# Breadboard_main.net
KiCad netlist of a schematic drawn in Altium Designer
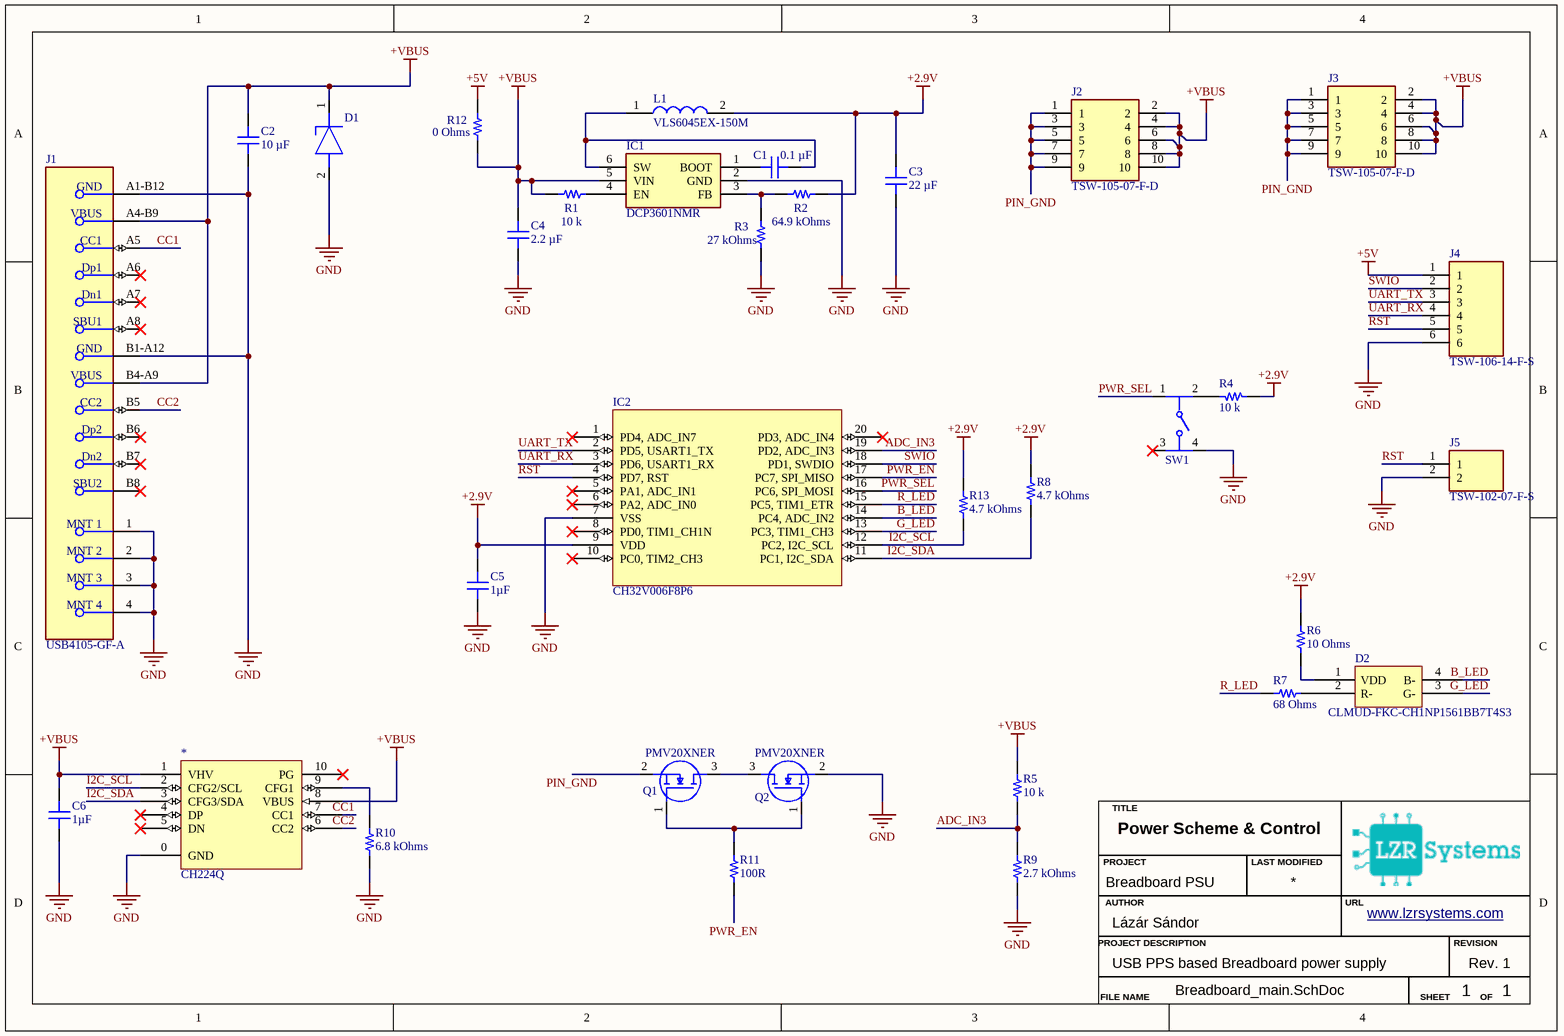
[diagram p0: Breadboard_main.SchDoc]

(export (version "E")
  (design (tool "Eeschema 10.0.6"))
  (components
    (comp (ref "*")
      (value "CH224Q")
      (footprint "SON40P200X75_HS-11N")
      (description "USB-PD 3.2 Sink Controller, EPR, PPS, AVS, I2C")
      (libsource (lib "Sandor Lazar") (part "New symbol 1"))
    )
    (comp (ref "C1")
      (value "0.1 µF")
      (footprint "CAP 0805_2012")
      (description "CAP CER 0.1UF 50V X7R 0805")
      (fields
        (field (name "PART NUMBER") "CC0805MRX7R9BB104")
        (field (name "CAPACITANCE") "0.1 µF")
        (field (name "MANUFACTURER") "Yageo")
      )
      (libsource (lib "Celestial Altium Library - altium_library") (part "Capacitor"))
    )
    (comp (ref "C2")
      (value "10 µF")
      (footprint "CAP 1206_3216 - 0.8MM")
      (description "CAP CER 10UF 25V X5R 1206")
      (fields
        (field (name "PART NUMBER") "TMK316ABJ106KD-T")
        (field (name "CAPACITANCE") "10 µF")
        (field (name "MANUFACTURER") "Taiyo Yuden")
      )
      (libsource (lib "Celestial Altium Library - altium_library") (part "Capacitor"))
    )
    (comp (ref "C3")
      (value "22 µF")
      (footprint "CAP 1206_3216 - 0.8MM")
      (description "CAP CER 22UF 16V X5R 1206")
      (fields
        (field (name "PART NUMBER") "CL31A226MOCLNNC")
        (field (name "CAPACITANCE") "22 µF")
        (field (name "MANUFACTURER") "Samsung Electro-Mechanics")
      )
      (libsource (lib "Celestial Altium Library - altium_library") (part "Capacitor"))
    )
    (comp (ref "C4")
      (value "2.2 µF")
      (footprint "CAP 1206_3216 - 0.8MM")
      (description "CAP CER 2.2UF 50V X7R 1206")
      (fields
        (field (name "PART NUMBER") "GCJ31CR71H225KA12K")
        (field (name "CAPACITANCE") "2.2 µF")
        (field (name "MANUFACTURER") "Murata Electronics")
      )
      (libsource (lib "Celestial Altium Library - altium_library") (part "Capacitor"))
    )
    (comp (ref "C5")
      (value "1µF")
      (footprint "CAP 1206_3216 - 1.0MM")
      (description "CAP CER 1UF 50V X7R 1206")
      (fields
        (field (name "PART NUMBER") "12065C105K4Z2A")
        (field (name "CAPACITANCE") "1µF")
        (field (name "MANUFACTURER") "AVX Corporation")
      )
      (libsource (lib "Celestial Altium Library - altium_library") (part "Capacitor"))
    )
    (comp (ref "C6")
      (value "1µF")
      (footprint "CAP 1206_3216 - 1.0MM")
      (description "CAP CER 1UF 50V X7R 1206")
      (fields
        (field (name "PART NUMBER") "12065C105K4Z2A")
        (field (name "CAPACITANCE") "1µF")
        (field (name "MANUFACTURER") "AVX Corporation")
      )
      (libsource (lib "Celestial Altium Library - altium_library") (part "Capacitor"))
    )
    (comp (ref "D1")
      (value "PESD24VS1UA,115")
      (footprint "SamacSys:SOD2512X110N")
      (description "Diode ESD (Uni-directional)")
      (fields (field (name "MOUSER PART NUMBER") "771-PESD24VS1UA115"))
      (libsource (lib "*") (part "PESD24VS1UA,115"))
    )
    (comp (ref "D2")
      (value "CLMUD-FKC-CH1NP1561BB7T4S3")
      (footprint "SON70P150X100-4N")
      (description "Cree LED RGB LED Common Annode If=10mA Vf = 1.9/2.6/2.7")
      (libsource (lib "Sandor Lazar") (part "CLMUD-FKC-CH1NP1561BB7T4S3-Symbol-1"))
    )
    (comp (ref "IC1")
      (value "DCP3601NMR")
      (footprint "SamacSys:SOT95P280X125-6N")
      (description "Integrated Circuit")
      (fields (field (name "MOUSER PART NUMBER") "511-DCP3601NMR"))
      (libsource (lib "*") (part "DCP3601NMR"))
    )
    (comp (ref "IC2")
      (value "CH32V006F8P6")
      (footprint "TSOP65P640X110-20N")
      (description "CH32V006 is an industrial-grade general-purpose microcontroller based on the QingKe RISC-V core.")
      (libsource (lib "") (part "New symbol 1_1"))
    )
    (comp (ref "J1")
      (value "USB4105-GF-A")
      (footprint "FP-USB4105-GF-A-MFG")
      (description "Conn USB 2.0 Type C RCP 24 POS 0.3mm/0.5mm Solder RA SMD 24 Terminal 1 Port T/R")
      (libsource (lib "Sandor Lazar") (part "e7c17a616881a82b79941196b4bec10"))
    )
    (comp (ref "J2")
      (value "TSW-105-07-F-D")
      (footprint "SamacSys:TSW-105-XX-YY-D")
      (description "Connector")
      (fields (field (name "MOUSER PART NUMBER") "200-TSW10507FD"))
      (libsource (lib "*") (part "TSW-105-07-F-D"))
    )
    (comp (ref "J3")
      (value "TSW-105-07-F-D")
      (footprint "SamacSys:TSW-105-XX-YY-D")
      (description "Connector")
      (fields (field (name "MOUSER PART NUMBER") "200-TSW10507FD"))
      (libsource (lib "*") (part "TSW-105-07-F-D"))
    )
    (comp (ref "J4")
      (value "TSW-106-14-F-S")
      (footprint "SamacSys:TSW-106-XX-YY-S")
      (description "Connector")
      (fields (field (name "MOUSER PART NUMBER") "200-TSW10614FS"))
      (libsource (lib "*") (part "TSW-106-14-F-S"))
    )
    (comp (ref "J5")
      (value "TSW-102-07-F-S")
      (footprint "SamacSys:TSW-102-XX-YY-S")
      (description "Connector")
      (fields (field (name "MOUSER PART NUMBER") "200-TSW10207FS"))
      (libsource (lib "*") (part "TSW-102-07-F-S"))
    )
    (comp (ref "L1")
      (value "VLS6045EX-150M")
      (footprint "SamacSys:VLS6045")
      (description "Inductor")
      (fields (field (name "MOUSER PART NUMBER") "810-VLS6045EX-150M"))
      (libsource (lib "SamacSys") (part "VLS6045EX-150M"))
    )
    (comp (ref "Q1")
      (value "PMV20XNER")
      (footprint "SamacSys:SOT95P230X110-3N")
      (description "MOSFET (N-Channel)")
      (fields (field (name "MOUSER PART NUMBER") "771-PMV20XNER"))
      (libsource (lib "SamacSys") (part "PMV20XNER"))
    )
    (comp (ref "Q2")
      (value "PMV20XNER")
      (footprint "SamacSys:SOT95P230X110-3N")
      (description "MOSFET (N-Channel)")
      (fields (field (name "MOUSER PART NUMBER") "771-PMV20XNER"))
      (libsource (lib "SamacSys") (part "PMV20XNER"))
    )
    (comp (ref "R1")
      (value "10 k")
      (footprint "RES 0805_2012")
      (description "RES 10K OHM 0.1% 1/10W 0805")
      (fields
        (field (name "PART NUMBER") "RNCS0805BKE10K0")
        (field (name "MANUFACTURER") "Stackpole Electronics Inc")
      )
      (libsource (lib "Celestial Altium Library - altium_library") (part "Resistor"))
    )
    (comp (ref "R2")
      (value "64.9 kOhms")
      (footprint "RES 0805_2012")
      (description "RES 64.9K OHM 1% 1/8W 0805")
      (fields
        (field (name "PART NUMBER") "RMCF0805FT64K9")
        (field (name "MANUFACTURER") "Stackpole Electronics Inc")
      )
      (libsource (lib "Celestial Altium Library - altium_library") (part "Resistor"))
    )
    (comp (ref "R3")
      (value "27 kOhms")
      (footprint "YAGEO RES 0805_2012")
      (description "RES SMD 27K OHM 5% 1/8W 0805")
      (fields (field (name "PART NUMBER") "AC0805JR-0727KL") (field (name "MANUFACTURER") "Yageo"))
      (libsource (lib "Celestial Altium Library - altium_library") (part "Resistor"))
    )
    (comp (ref "R4")
      (value "10 k")
      (footprint "RES 0805_2012")
      (description "RES 10K OHM 0.1% 1/10W 0805")
      (fields
        (field (name "PART NUMBER") "RNCS0805BKE10K0")
        (field (name "MANUFACTURER") "Stackpole Electronics Inc")
      )
      (libsource (lib "Celestial Altium Library - altium_library") (part "Resistor"))
    )
    (comp (ref "R5")
      (value "10 k")
      (footprint "RES 0805_2012")
      (description "RES 10K OHM 0.1% 1/10W 0805")
      (fields
        (field (name "PART NUMBER") "RNCS0805BKE10K0")
        (field (name "MANUFACTURER") "Stackpole Electronics Inc")
      )
      (libsource (lib "Celestial Altium Library - altium_library") (part "Resistor"))
    )
    (comp (ref "R6")
      (value "10 Ohms")
      (footprint "YAGEO RES 0805_2012")
      (description "RES 10 OHM 5% 1/8W 0805")
      (fields (field (name "PART NUMBER") "RC0805JR-0710RL") (field (name "MANUFACTURER") "Yageo"))
      (libsource (lib "Celestial Altium Library - altium_library") (part "Resistor"))
    )
    (comp (ref "R7")
      (value "68 Ohms")
      (footprint "RES 0805_2012")
      (description "RES 68 OHM 1% 1/3W 0805")
      (fields
        (field (name "PART NUMBER") "CRGP0805F68R")
        (field (name "MANUFACTURER") "TE Connectivity Passive Product")
      )
      (libsource (lib "Celestial Altium Library - altium_library") (part "Resistor"))
    )
    (comp (ref "R8")
      (value "4.7 kOhms")
      (footprint "RES 0805_2012")
      (description "RES 4.7 KOHM 0.05% 1/8W 0805")
      (fields (field (name "PART NUMBER") "TNPU08054K70AYEA00") (field (name "MANUFACTURER") "Vishay Dale"))
      (libsource (lib "Celestial Altium Library - altium_library") (part "Resistor"))
    )
    (comp (ref "R9")
      (value "2.7 kOhms")
      (footprint "YAGEO RES 0805_2012")
      (description "RES 2.7K OHM 1% 1/8W 0805")
      (fields (field (name "PART NUMBER") "RC0805FR-132K7L") (field (name "MANUFACTURER") "Yageo"))
      (libsource (lib "Celestial Altium Library - altium_library") (part "Resistor"))
    )
    (comp (ref "R10")
      (value "6.8 kOhms")
      (footprint "RES 0805_2012")
      (description "RES SMD 6.8K OHM 1% 1/8W 0805")
      (fields
        (field (name "PART NUMBER") "ERJ-6ENF6801V")
        (field (name "MANUFACTURER") "Panasonic Electronic Components")
      )
      (libsource (lib "Celestial Altium Library - altium_library") (part "Resistor"))
    )
    (comp (ref "R11")
      (value "100R")
      (footprint "RES 0805_2012")
      (description "RES SMD 180 OHM 1% 1/2W 0805")
      (fields (field (name "PART NUMBER") "CRCW0805180RFKEAHP") (field (name "MANUFACTURER") "Vishay Dale"))
      (libsource (lib "Celestial Altium Library - altium_library") (part "Resistor"))
    )
    (comp (ref "R12")
      (value "0 Ohms")
      (footprint "YAGEO RES 0805_2012")
      (description "RES 0 OHM JUMPER 1/8W 0805")
      (fields (field (name "PART NUMBER") "RC0805FR-070RL") (field (name "MANUFACTURER") "Yageo"))
      (libsource (lib "Celestial Altium Library - altium_library") (part "Resistor"))
    )
    (comp (ref "R13")
      (value "4.7 kOhms")
      (footprint "RES 0805_2012")
      (description "RES 4.7 KOHM 0.05% 1/8W 0805")
      (fields (field (name "PART NUMBER") "TNPU08054K70AYEA00") (field (name "MANUFACTURER") "Vishay Dale"))
      (libsource (lib "Celestial Altium Library - altium_library") (part "Resistor"))
    )
    (comp (ref "SW1")
      (value "TL1105AF160Q")
      (footprint "FP-TL1105AF160Q-MFG")
      (description "Switch Tactile N.O. SPST Round Button PC Pins 0.05A 50VDC 1.57N Thru-Hole")
      (libsource (lib "Sandor Lazar") (part "82b636f13fd696edb7519609c0a8a76"))
    )
  )
  (nets
    (net (code "1") (name "+2.9V") (class "Default")
      (node (ref "C3") (pin "2") (pinfunction "2_2") (pintype "passive"))
      (node (ref "C5") (pin "2") (pinfunction "2_2") (pintype "passive"))
      (node (ref "IC2") (pin "9") (pinfunction "VDD_9") (pintype "power_in"))
      (node (ref "L1") (pin "2") (pinfunction "2_2") (pintype "passive"))
      (node (ref "R13") (pin "2") (pinfunction "2_2") (pintype "passive"))
      (node (ref "R2") (pin "2") (pinfunction "2_2") (pintype "passive"))
      (node (ref "R4") (pin "2") (pinfunction "2_2") (pintype "passive"))
      (node (ref "R6") (pin "2") (pinfunction "2_2") (pintype "passive"))
      (node (ref "R8") (pin "2") (pinfunction "2_2") (pintype "passive"))
    )
    (net (code "2") (name "+5V") (class "Default")
      (node (ref "J4") (pin "1") (pinfunction "1_1") (pintype "passive"))
      (node (ref "R12") (pin "1") (pinfunction "1_1") (pintype "passive"))
    )
    (net (code "3") (name "+VBUS") (class "Default")
      (node (ref "*") (pin "1") (pinfunction "VHV_1") (pintype "power_in"))
      (node (ref "*") (pin "8") (pinfunction "VBUS_8") (pintype "input"))
      (node (ref "C2") (pin "2") (pinfunction "2_2") (pintype "passive"))
      (node (ref "C4") (pin "2") (pinfunction "2_2") (pintype "passive"))
      (node (ref "C6") (pin "2") (pinfunction "2_2") (pintype "passive"))
      (node (ref "D1") (pin "1") (pinfunction "K_1") (pintype "passive"))
      (node (ref "IC1") (pin "5") (pinfunction "VIN_5") (pintype "passive"))
      (node (ref "J1") (pin "A4-B9") (pinfunction "VBUS_A4-B9") (pintype "power_in"))
      (node (ref "J1") (pin "B4-A9") (pinfunction "VBUS_B4-A9") (pintype "power_in"))
      (node (ref "J2") (pin "10") (pinfunction "10_10") (pintype "passive"))
      (node (ref "J2") (pin "2") (pinfunction "2_2") (pintype "passive"))
      (node (ref "J2") (pin "4") (pinfunction "4_4") (pintype "passive"))
      (node (ref "J2") (pin "6") (pinfunction "6_6") (pintype "passive"))
      (node (ref "J2") (pin "8") (pinfunction "8_8") (pintype "passive"))
      (node (ref "J3") (pin "10") (pinfunction "10_10") (pintype "passive"))
      (node (ref "J3") (pin "2") (pinfunction "2_2") (pintype "passive"))
      (node (ref "J3") (pin "4") (pinfunction "4_4") (pintype "passive"))
      (node (ref "J3") (pin "6") (pinfunction "6_6") (pintype "passive"))
      (node (ref "J3") (pin "8") (pinfunction "8_8") (pintype "passive"))
      (node (ref "R1") (pin "1") (pinfunction "1_1") (pintype "passive"))
      (node (ref "R12") (pin "2") (pinfunction "2_2") (pintype "passive"))
      (node (ref "R5") (pin "1") (pinfunction "1_1") (pintype "passive"))
    )
    (net (code "4") (name "/ADC_IN3") (class "Default")
      (node (ref "IC2") (pin "19") (pinfunction "PD2,_ADC_IN3_19") (pintype "bidirectional"))
      (node (ref "R5") (pin "2") (pinfunction "2_2") (pintype "passive"))
      (node (ref "R9") (pin "1") (pinfunction "1_1") (pintype "passive"))
    )
    (net (code "5") (name "/B_LED") (class "Default")
      (node (ref "D2") (pin "4") (pinfunction "B-_4") (pintype "passive"))
      (node (ref "IC2") (pin "14") (pinfunction "PC4,_ADC_IN2_14") (pintype "bidirectional"))
    )
    (net (code "6") (name "/CC1") (class "Default")
      (node (ref "*") (pin "7") (pinfunction "CC1_7") (pintype "bidirectional"))
      (node (ref "J1") (pin "A5") (pinfunction "CC1_A5") (pintype "bidirectional"))
    )
    (net (code "7") (name "/CC2") (class "Default")
      (node (ref "*") (pin "6") (pinfunction "CC2_6") (pintype "bidirectional"))
      (node (ref "J1") (pin "B5") (pinfunction "CC2_B5") (pintype "bidirectional"))
    )
    (net (code "8") (name "/G_LED") (class "Default")
      (node (ref "D2") (pin "3") (pinfunction "G-_3") (pintype "passive"))
      (node (ref "IC2") (pin "13") (pinfunction "PC3,_TIM1_CH3_13") (pintype "bidirectional"))
    )
    (net (code "9") (name "/I2C_SCL") (class "Default")
      (node (ref "*") (pin "2") (pinfunction "CFG2/SCL_2") (pintype "bidirectional"))
      (node (ref "IC2") (pin "12") (pinfunction "PC2,_I2C_SCL_12") (pintype "bidirectional"))
      (node (ref "R13") (pin "1") (pinfunction "1_1") (pintype "passive"))
    )
    (net (code "10") (name "/I2C_SDA") (class "Default")
      (node (ref "*") (pin "3") (pinfunction "CFG3/SDA_3") (pintype "bidirectional"))
      (node (ref "IC2") (pin "11") (pinfunction "PC1,_I2C_SDA_11") (pintype "bidirectional"))
      (node (ref "R8") (pin "1") (pinfunction "1_1") (pintype "passive"))
    )
    (net (code "11") (name "/PIN_GND") (class "Default")
      (node (ref "J2") (pin "1") (pinfunction "1_1") (pintype "passive"))
      (node (ref "J2") (pin "3") (pinfunction "3_3") (pintype "passive"))
      (node (ref "J2") (pin "5") (pinfunction "5_5") (pintype "passive"))
      (node (ref "J2") (pin "7") (pinfunction "7_7") (pintype "passive"))
      (node (ref "J2") (pin "9") (pinfunction "9_9") (pintype "passive"))
      (node (ref "J3") (pin "1") (pinfunction "1_1") (pintype "passive"))
      (node (ref "J3") (pin "3") (pinfunction "3_3") (pintype "passive"))
      (node (ref "J3") (pin "5") (pinfunction "5_5") (pintype "passive"))
      (node (ref "J3") (pin "7") (pinfunction "7_7") (pintype "passive"))
      (node (ref "J3") (pin "9") (pinfunction "9_9") (pintype "passive"))
      (node (ref "Q1") (pin "2") (pinfunction "S_2") (pintype "passive"))
    )
    (net (code "12") (name "/PWR_EN") (class "Default")
      (node (ref "IC2") (pin "17") (pinfunction "PC7,_SPI_MISO_17") (pintype "bidirectional"))
      (node (ref "R11") (pin "1") (pinfunction "1_1") (pintype "passive"))
    )
    (net (code "13") (name "/PWR_SEL") (class "Default")
      (node (ref "IC2") (pin "16") (pinfunction "PC6,_SPI_MOSI_16") (pintype "bidirectional"))
      (node (ref "SW1") (pin "1") (pinfunction "1_1") (pintype "passive"))
    )
    (net (code "14") (name "/RST") (class "Default")
      (node (ref "IC2") (pin "4") (pinfunction "PD7,_RST_4") (pintype "bidirectional"))
      (node (ref "J4") (pin "5") (pinfunction "5_5") (pintype "passive"))
      (node (ref "J5") (pin "1") (pinfunction "1_1") (pintype "passive"))
    )
    (net (code "15") (name "/R_LED") (class "Default")
      (node (ref "IC2") (pin "15") (pinfunction "PC5,_TIM1_ETR_15") (pintype "bidirectional"))
      (node (ref "R7") (pin "2") (pinfunction "2_2") (pintype "passive"))
    )
    (net (code "16") (name "/SWIO") (class "Default")
      (node (ref "IC2") (pin "18") (pinfunction "PD1,_SWDIO_18") (pintype "bidirectional"))
      (node (ref "J4") (pin "2") (pinfunction "2_2") (pintype "passive"))
    )
    (net (code "17") (name "/UART_RX") (class "Default")
      (node (ref "IC2") (pin "3") (pinfunction "PD6,_USART1_RX_3") (pintype "bidirectional"))
      (node (ref "J4") (pin "4") (pinfunction "4_4") (pintype "passive"))
    )
    (net (code "18") (name "/UART_TX") (class "Default")
      (node (ref "IC2") (pin "2") (pinfunction "PD5,_USART1_TX_2") (pintype "bidirectional"))
      (node (ref "J4") (pin "3") (pinfunction "3_3") (pintype "passive"))
    )
    (net (code "19") (name "GND") (class "Default")
      (node (ref "*") (pin "0") (pinfunction "GND_0") (pintype "power_in"))
      (node (ref "C2") (pin "1") (pinfunction "1_1") (pintype "passive"))
      (node (ref "C3") (pin "1") (pinfunction "1_1") (pintype "passive"))
      (node (ref "C4") (pin "1") (pinfunction "1_1") (pintype "passive"))
      (node (ref "C5") (pin "1") (pinfunction "1_1") (pintype "passive"))
      (node (ref "C6") (pin "1") (pinfunction "1_1") (pintype "passive"))
      (node (ref "D1") (pin "2") (pinfunction "A_2") (pintype "passive"))
      (node (ref "IC1") (pin "2") (pinfunction "GND_2") (pintype "passive"))
      (node (ref "IC2") (pin "7") (pinfunction "VSS_7") (pintype "power_in"))
      (node (ref "J1") (pin "1") (pinfunction "MNT_1_1") (pintype "passive"))
      (node (ref "J1") (pin "2") (pinfunction "MNT_2_2") (pintype "passive"))
      (node (ref "J1") (pin "3") (pinfunction "MNT_3_3") (pintype "passive"))
      (node (ref "J1") (pin "4") (pinfunction "MNT_4_4") (pintype "passive"))
      (node (ref "J1") (pin "A1-B12") (pinfunction "GND_A1-B12") (pintype "power_in"))
      (node (ref "J1") (pin "B1-A12") (pinfunction "GND_B1-A12") (pintype "power_in"))
      (node (ref "J4") (pin "6") (pinfunction "6_6") (pintype "passive"))
      (node (ref "J5") (pin "2") (pinfunction "2_2") (pintype "passive"))
      (node (ref "Q2") (pin "2") (pinfunction "S_2") (pintype "passive"))
      (node (ref "R10") (pin "1") (pinfunction "1_1") (pintype "passive"))
      (node (ref "R3") (pin "1") (pinfunction "1_1") (pintype "passive"))
      (node (ref "R9") (pin "2") (pinfunction "2_2") (pintype "passive"))
      (node (ref "SW1") (pin "4") (pinfunction "4_4") (pintype "passive"))
    )
    (net (code "20") (name "Net-(*-CFG1)") (class "Default")
      (node (ref "*") (pin "9") (pinfunction "CFG1_9") (pintype "bidirectional"))
      (node (ref "R10") (pin "2") (pinfunction "2_2") (pintype "passive"))
    )
    (net (code "21") (name "Net-(D2-R-)") (class "Default")
      (node (ref "D2") (pin "2") (pinfunction "R-_2") (pintype "passive"))
      (node (ref "R7") (pin "1") (pinfunction "1_1") (pintype "passive"))
    )
    (net (code "22") (name "Net-(D2-VDD)") (class "Default")
      (node (ref "D2") (pin "1") (pinfunction "VDD_1") (pintype "passive"))
      (node (ref "R6") (pin "1") (pinfunction "1_1") (pintype "passive"))
    )
    (net (code "23") (name "Net-(IC1-BOOT)") (class "Default")
      (node (ref "C1") (pin "1") (pinfunction "1_1") (pintype "passive"))
      (node (ref "IC1") (pin "1") (pinfunction "BOOT_1") (pintype "passive"))
    )
    (net (code "24") (name "Net-(IC1-EN)") (class "Default")
      (node (ref "IC1") (pin "4") (pinfunction "EN_4") (pintype "passive"))
      (node (ref "R1") (pin "2") (pinfunction "2_2") (pintype "passive"))
    )
    (net (code "25") (name "Net-(IC1-FB)") (class "Default")
      (node (ref "IC1") (pin "3") (pinfunction "FB_3") (pintype "passive"))
      (node (ref "R2") (pin "1") (pinfunction "1_1") (pintype "passive"))
      (node (ref "R3") (pin "2") (pinfunction "2_2") (pintype "passive"))
    )
    (net (code "26") (name "Net-(IC1-SW)") (class "Default")
      (node (ref "C1") (pin "2") (pinfunction "2_2") (pintype "passive"))
      (node (ref "IC1") (pin "6") (pinfunction "SW_6") (pintype "passive"))
      (node (ref "L1") (pin "1") (pinfunction "1_1") (pintype "passive"))
    )
    (net (code "27") (name "Net-(Q1-D)") (class "Default")
      (node (ref "Q1") (pin "3") (pinfunction "D_3") (pintype "passive"))
      (node (ref "Q2") (pin "3") (pinfunction "D_3") (pintype "passive"))
    )
    (net (code "28") (name "Net-(Q1-G)") (class "Default")
      (node (ref "Q1") (pin "1") (pinfunction "G_1") (pintype "passive"))
      (node (ref "Q2") (pin "1") (pinfunction "G_1") (pintype "passive"))
      (node (ref "R11") (pin "2") (pinfunction "2_2") (pintype "passive"))
    )
    (net (code "29") (name "Net-(R4-Pad1)") (class "Default")
      (node (ref "R4") (pin "1") (pinfunction "1_1") (pintype "passive"))
      (node (ref "SW1") (pin "2") (pinfunction "2_2") (pintype "passive"))
    )
    (net (code "30") (name "unconnected-(*-DN-Pad5)") (class "Default")
      (node (ref "*") (pin "5") (pinfunction "DN_5") (pintype "bidirectional+no_connect"))
    )
    (net (code "31") (name "unconnected-(*-DP-Pad4)") (class "Default")
      (node (ref "*") (pin "4") (pinfunction "DP_4") (pintype "bidirectional+no_connect"))
    )
    (net (code "32") (name "unconnected-(*-PG-Pad10)") (class "Default")
      (node (ref "*") (pin "10") (pinfunction "PG_10") (pintype "open_collector+no_connect"))
    )
    (net (code "33") (name "unconnected-(IC2-PA1,_ADC_IN1-Pad5)") (class "Default")
      (node (ref "IC2") (pin "5") (pinfunction "PA1,_ADC_IN1_5") (pintype "bidirectional+no_connect"))
    )
    (net (code "34") (name "unconnected-(IC2-PA2,_ADC_IN0-Pad6)") (class "Default")
      (node (ref "IC2") (pin "6") (pinfunction "PA2,_ADC_IN0_6") (pintype "bidirectional+no_connect"))
    )
    (net (code "35") (name "unconnected-(IC2-PC0,_TIM2_CH3-Pad10)") (class "Default")
      (node (ref "IC2") (pin "10") (pinfunction "PC0,_TIM2_CH3_10") (pintype "bidirectional+no_connect"))
    )
    (net (code "36") (name "unconnected-(IC2-PD0,_TIM1_CH1N-Pad8)") (class "Default")
      (node (ref "IC2") (pin "8") (pinfunction "PD0,_TIM1_CH1N_8") (pintype "bidirectional+no_connect"))
    )
    (net (code "37") (name "unconnected-(IC2-PD3,_ADC_IN4-Pad20)") (class "Default")
      (node (ref "IC2") (pin "20") (pinfunction "PD3,_ADC_IN4_20") (pintype "bidirectional+no_connect"))
    )
    (net (code "38") (name "unconnected-(IC2-PD4,_ADC_IN7-Pad1)") (class "Default")
      (node (ref "IC2") (pin "1") (pinfunction "PD4,_ADC_IN7_1") (pintype "bidirectional+no_connect"))
    )
    (net (code "39") (name "unconnected-(J1-Dn1-PadA7)") (class "Default")
      (node (ref "J1") (pin "A7") (pinfunction "Dn1_A7") (pintype "bidirectional+no_connect"))
    )
    (net (code "40") (name "unconnected-(J1-Dn2-PadB7)") (class "Default")
      (node (ref "J1") (pin "B7") (pinfunction "Dn2_B7") (pintype "bidirectional+no_connect"))
    )
    (net (code "41") (name "unconnected-(J1-Dp1-PadA6)") (class "Default")
      (node (ref "J1") (pin "A6") (pinfunction "Dp1_A6") (pintype "bidirectional+no_connect"))
    )
    (net (code "42") (name "unconnected-(J1-Dp2-PadB6)") (class "Default")
      (node (ref "J1") (pin "B6") (pinfunction "Dp2_B6") (pintype "bidirectional+no_connect"))
    )
    (net (code "43") (name "unconnected-(J1-SBU1-PadA8)") (class "Default")
      (node (ref "J1") (pin "A8") (pinfunction "SBU1_A8") (pintype "bidirectional+no_connect"))
    )
    (net (code "44") (name "unconnected-(J1-SBU2-PadB8)") (class "Default")
      (node (ref "J1") (pin "B8") (pinfunction "SBU2_B8") (pintype "power_in+no_connect"))
    )
    (net (code "45") (name "unconnected-(SW1-Pad3)") (class "Default")
      (node (ref "SW1") (pin "3") (pinfunction "3_3") (pintype "passive+no_connect"))
    )
  )
)
